# stock.net
KiCad netlist of a schematic drawn in EAGLE
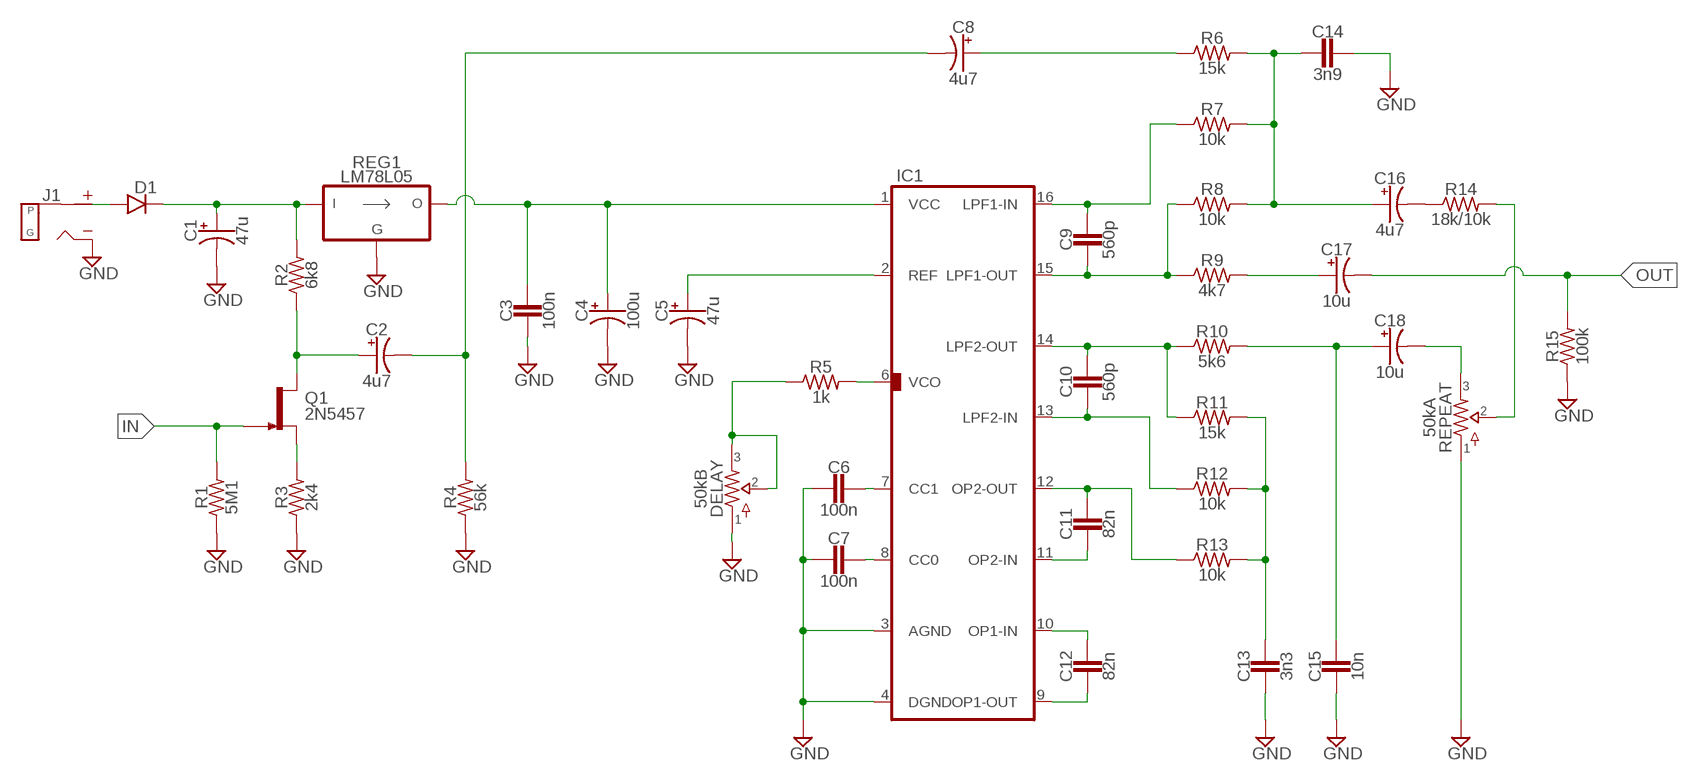
[diagram p0: schematic, sheet 1]

(export (version "E")
  (design (tool "Eeschema 10.0.6"))
  (components
    (comp (ref "C1")
      (value "47u")
      (footprint "eagle-import:050_020_1")
      (libsource (lib "eagle-import") (part "0501"))
    )
    (comp (ref "C2")
      (value "4u7")
      (footprint "eagle-import:050_020_1")
      (libsource (lib "eagle-import") (part "0501"))
    )
    (comp (ref "C3")
      (value "100n")
      (footprint "eagle-import:050X030_025_2")
      (libsource (lib "eagle-import") (part "CER/FILM2"))
    )
    (comp (ref "C4")
      (value "100u")
      (footprint "eagle-import:050_020_1")
      (libsource (lib "eagle-import") (part "0501"))
    )
    (comp (ref "C5")
      (value "47u")
      (footprint "eagle-import:050_020_1")
      (libsource (lib "eagle-import") (part "0501"))
    )
    (comp (ref "C6")
      (value "100n")
      (footprint "eagle-import:050X030_025_2")
      (libsource (lib "eagle-import") (part "CER/FILM2"))
    )
    (comp (ref "C7")
      (value "100n")
      (footprint "eagle-import:050X030_025_2")
      (libsource (lib "eagle-import") (part "CER/FILM2"))
    )
    (comp (ref "C8")
      (value "4u7")
      (footprint "eagle-import:050_020_1")
      (libsource (lib "eagle-import") (part "0501"))
    )
    (comp (ref "C9")
      (value "560p")
      (footprint "eagle-import:050X030_025_2")
      (libsource (lib "eagle-import") (part "CER/FILM2"))
    )
    (comp (ref "C10")
      (value "560p")
      (footprint "eagle-import:050X030_025_2")
      (libsource (lib "eagle-import") (part "CER/FILM2"))
    )
    (comp (ref "C11")
      (value "82n")
      (footprint "eagle-import:050X030_025_2")
      (libsource (lib "eagle-import") (part "CER/FILM2"))
    )
    (comp (ref "C12")
      (value "82n")
      (footprint "eagle-import:050X030_025_2")
      (libsource (lib "eagle-import") (part "CER/FILM2"))
    )
    (comp (ref "C13")
      (value "3n3")
      (footprint "eagle-import:050X030_025_2")
      (libsource (lib "eagle-import") (part "CER/FILM2"))
    )
    (comp (ref "C14")
      (value "3n9")
      (footprint "eagle-import:050X030_025_2")
      (libsource (lib "eagle-import") (part "CER/FILM2"))
    )
    (comp (ref "C15")
      (value "10n")
      (footprint "eagle-import:050X030_025_2")
      (libsource (lib "eagle-import") (part "CER/FILM2"))
    )
    (comp (ref "C16")
      (value "4u7")
      (footprint "eagle-import:050_020_1")
      (libsource (lib "eagle-import") (part "0501"))
    )
    (comp (ref "C17")
      (value "10u")
      (footprint "eagle-import:050_020_1")
      (libsource (lib "eagle-import") (part "0501"))
    )
    (comp (ref "C18")
      (value "10u")
      (footprint "eagle-import:050_020_1")
      (libsource (lib "eagle-import") (part "0501"))
    )
    (comp (ref "D1")
      (value "DO41.3")
      (footprint "eagle-import:DO41-3")
      (libsource (lib "eagle-import") (part "DO41.3"))
    )
    (comp (ref "DELAY")
      (value "50kB")
      (footprint "eagle-import:PADS_SMALL")
      (libsource (lib "eagle-import") (part "POTSSMALL_PADS"))
    )
    (comp (ref "IC1")
      (value "PT2399TH")
      (footprint "eagle-import:DIL16")
      (libsource (lib "eagle-import") (part "PT2399TH"))
    )
    (comp (ref "J1")
      (value "DC_MONO")
      (footprint "eagle-import:DC")
      (libsource (lib "eagle-import") (part "DC_MONO"))
    )
    (comp (ref "Q1")
      (value "2N5457")
      (footprint "eagle-import:TO92-")
      (libsource (lib "eagle-import") (part "2N5457"))
    )
    (comp (ref "R1")
      (value "5M1")
      (footprint "eagle-import:R0207_2V")
      (libsource (lib "eagle-import") (part "R_.2"))
    )
    (comp (ref "R2")
      (value "6k8")
      (footprint "eagle-import:R0207_2V")
      (libsource (lib "eagle-import") (part "R_.2"))
    )
    (comp (ref "R3")
      (value "2k4")
      (footprint "eagle-import:R0207_2V")
      (libsource (lib "eagle-import") (part "R_.2"))
    )
    (comp (ref "R4")
      (value "56k")
      (footprint "eagle-import:R0207_2V")
      (libsource (lib "eagle-import") (part "R_.2"))
    )
    (comp (ref "R5")
      (value "1k")
      (footprint "eagle-import:R0207_2V")
      (libsource (lib "eagle-import") (part "R_.2"))
    )
    (comp (ref "R6")
      (value "15k")
      (footprint "eagle-import:R0207_2V")
      (libsource (lib "eagle-import") (part "R_.2"))
    )
    (comp (ref "R7")
      (value "10k")
      (footprint "eagle-import:R0207_2V")
      (libsource (lib "eagle-import") (part "R_.2"))
    )
    (comp (ref "R8")
      (value "10k")
      (footprint "eagle-import:R0207_2V")
      (libsource (lib "eagle-import") (part "R_.2"))
    )
    (comp (ref "R9")
      (value "4k7")
      (footprint "eagle-import:R0207_2V")
      (libsource (lib "eagle-import") (part "R_.2"))
    )
    (comp (ref "R10")
      (value "5k6")
      (footprint "eagle-import:R0207_2V")
      (libsource (lib "eagle-import") (part "R_.2"))
    )
    (comp (ref "R11")
      (value "15k")
      (footprint "eagle-import:R0207_2V")
      (libsource (lib "eagle-import") (part "R_.2"))
    )
    (comp (ref "R12")
      (value "10k")
      (footprint "eagle-import:R0207_2V")
      (libsource (lib "eagle-import") (part "R_.2"))
    )
    (comp (ref "R13")
      (value "10k")
      (footprint "eagle-import:R0207_2V")
      (libsource (lib "eagle-import") (part "R_.2"))
    )
    (comp (ref "R14")
      (value "18k/10k")
      (footprint "eagle-import:R0207_2V")
      (libsource (lib "eagle-import") (part "R_.2"))
    )
    (comp (ref "R15")
      (value "100k")
      (footprint "eagle-import:R0207_2V")
      (libsource (lib "eagle-import") (part "R_.2"))
    )
    (comp (ref "REG1")
      (value "LM78L05")
      (footprint "eagle-import:TO92-")
      (libsource (lib "eagle-import") (part "LM78L05"))
    )
    (comp (ref "REPEAT")
      (value "50kA")
      (footprint "eagle-import:PADS_SMALL")
      (libsource (lib "eagle-import") (part "POTSSMALL_PADS"))
    )
  )
  (nets
    (net (code "1") (name "GND") (class "Default")
      (node (ref "C1") (pin "-") (pinfunction "-_-") (pintype "passive"))
      (node (ref "C13") (pin "2") (pinfunction "2_2") (pintype "passive"))
      (node (ref "C14") (pin "1") (pinfunction "1_1") (pintype "passive"))
      (node (ref "C15") (pin "2") (pinfunction "2_2") (pintype "passive"))
      (node (ref "C3") (pin "2") (pinfunction "2_2") (pintype "passive"))
      (node (ref "C4") (pin "-") (pinfunction "-_-") (pintype "passive"))
      (node (ref "C5") (pin "-") (pinfunction "-_-") (pintype "passive"))
      (node (ref "C6") (pin "2") (pinfunction "2_2") (pintype "passive"))
      (node (ref "C7") (pin "2") (pinfunction "2_2") (pintype "passive"))
      (node (ref "DELAY") (pin "1") (pinfunction "1_1") (pintype "passive"))
      (node (ref "IC1") (pin "3") (pinfunction "AGND_3") (pintype "power_in"))
      (node (ref "IC1") (pin "4") (pinfunction "DGND_4") (pintype "power_in"))
      (node (ref "J1") (pin "S") (pinfunction "SLEEVE_S") (pintype "passive"))
      (node (ref "R1") (pin "1") (pinfunction "1_1") (pintype "passive"))
      (node (ref "R15") (pin "1") (pinfunction "1_1") (pintype "passive"))
      (node (ref "R3") (pin "1") (pinfunction "1_1") (pintype "passive"))
      (node (ref "R4") (pin "1") (pinfunction "1_1") (pintype "passive"))
      (node (ref "REG1") (pin "2") (pinfunction "GND_2") (pintype "passive"))
      (node (ref "REPEAT") (pin "1") (pinfunction "1_1") (pintype "passive"))
    )
    (net (code "2") (name "IN") (class "Default")
      (node (ref "Q1") (pin "1") (pinfunction "G_1") (pintype "passive"))
      (node (ref "R1") (pin "2") (pinfunction "2_2") (pintype "passive"))
    )
    (net (code "3") (name "Net-(C2-Pad-)") (class "Default")
      (node (ref "C2") (pin "-") (pinfunction "-_-") (pintype "passive"))
      (node (ref "C8") (pin "-") (pinfunction "-_-") (pintype "passive"))
      (node (ref "R4") (pin "2") (pinfunction "2_2") (pintype "passive"))
    )
    (net (code "4") (name "Net-(C8-Pad+)") (class "Default")
      (node (ref "C8") (pin "+") (pinfunction "+_+") (pintype "passive"))
      (node (ref "R6") (pin "1") (pinfunction "1_1") (pintype "passive"))
    )
    (net (code "5") (name "Net-(C13-Pad1)") (class "Default")
      (node (ref "C13") (pin "1") (pinfunction "1_1") (pintype "passive"))
      (node (ref "R11") (pin "2") (pinfunction "2_2") (pintype "passive"))
      (node (ref "R12") (pin "2") (pinfunction "2_2") (pintype "passive"))
      (node (ref "R13") (pin "2") (pinfunction "2_2") (pintype "passive"))
    )
    (net (code "6") (name "Net-(C14-Pad2)") (class "Default")
      (node (ref "C14") (pin "2") (pinfunction "2_2") (pintype "passive"))
      (node (ref "C16") (pin "+") (pinfunction "+_+") (pintype "passive"))
      (node (ref "R6") (pin "2") (pinfunction "2_2") (pintype "passive"))
      (node (ref "R7") (pin "2") (pinfunction "2_2") (pintype "passive"))
      (node (ref "R8") (pin "2") (pinfunction "2_2") (pintype "passive"))
    )
    (net (code "7") (name "Net-(C15-Pad1)") (class "Default")
      (node (ref "C15") (pin "1") (pinfunction "1_1") (pintype "passive"))
      (node (ref "C18") (pin "+") (pinfunction "+_+") (pintype "passive"))
      (node (ref "R10") (pin "2") (pinfunction "2_2") (pintype "passive"))
    )
    (net (code "8") (name "Net-(C16-Pad-)") (class "Default")
      (node (ref "C16") (pin "-") (pinfunction "-_-") (pintype "passive"))
      (node (ref "R14") (pin "1") (pinfunction "1_1") (pintype "passive"))
    )
    (net (code "9") (name "Net-(C17-Pad+)") (class "Default")
      (node (ref "C17") (pin "+") (pinfunction "+_+") (pintype "passive"))
      (node (ref "R9") (pin "2") (pinfunction "2_2") (pintype "passive"))
    )
    (net (code "10") (name "Net-(C18-Pad-)") (class "Default")
      (node (ref "C18") (pin "-") (pinfunction "-_-") (pintype "passive"))
      (node (ref "REPEAT") (pin "3") (pinfunction "3_3") (pintype "passive"))
    )
    (net (code "11") (name "Net-(DELAY-Pad2)") (class "Default")
      (node (ref "DELAY") (pin "2") (pinfunction "2_2") (pintype "passive"))
      (node (ref "DELAY") (pin "3") (pinfunction "3_3") (pintype "passive"))
      (node (ref "R5") (pin "1") (pinfunction "1_1") (pintype "passive"))
    )
    (net (code "12") (name "Net-(IC1-CC0)") (class "Default")
      (node (ref "C7") (pin "1") (pinfunction "1_1") (pintype "passive"))
      (node (ref "IC1") (pin "8") (pinfunction "CC0_8") (pintype "input"))
    )
    (net (code "13") (name "Net-(IC1-CC1)") (class "Default")
      (node (ref "C6") (pin "1") (pinfunction "1_1") (pintype "passive"))
      (node (ref "IC1") (pin "7") (pinfunction "CC1_7") (pintype "input"))
    )
    (net (code "14") (name "Net-(IC1-LPF1-IN)") (class "Default")
      (node (ref "C9") (pin "1") (pinfunction "1_1") (pintype "passive"))
      (node (ref "IC1") (pin "16") (pinfunction "LPF1-IN_16") (pintype "input"))
      (node (ref "R7") (pin "1") (pinfunction "1_1") (pintype "passive"))
    )
    (net (code "15") (name "Net-(IC1-LPF1-OUT)") (class "Default")
      (node (ref "C9") (pin "2") (pinfunction "2_2") (pintype "passive"))
      (node (ref "IC1") (pin "15") (pinfunction "LPF1-OUT_15") (pintype "output"))
      (node (ref "R8") (pin "1") (pinfunction "1_1") (pintype "passive"))
      (node (ref "R9") (pin "1") (pinfunction "1_1") (pintype "passive"))
    )
    (net (code "16") (name "Net-(IC1-LPF2-IN)") (class "Default")
      (node (ref "C10") (pin "2") (pinfunction "2_2") (pintype "passive"))
      (node (ref "IC1") (pin "13") (pinfunction "LPF2-IN_13") (pintype "input"))
      (node (ref "R12") (pin "1") (pinfunction "1_1") (pintype "passive"))
    )
    (net (code "17") (name "Net-(IC1-LPF2-OUT)") (class "Default")
      (node (ref "C10") (pin "1") (pinfunction "1_1") (pintype "passive"))
      (node (ref "IC1") (pin "14") (pinfunction "LPF2-OUT_14") (pintype "output"))
      (node (ref "R10") (pin "1") (pinfunction "1_1") (pintype "passive"))
      (node (ref "R11") (pin "1") (pinfunction "1_1") (pintype "passive"))
    )
    (net (code "18") (name "Net-(IC1-OP1-IN)") (class "Default")
      (node (ref "C12") (pin "1") (pinfunction "1_1") (pintype "passive"))
      (node (ref "IC1") (pin "10") (pinfunction "OP1-IN_10") (pintype "input"))
    )
    (net (code "19") (name "Net-(IC1-OP1-OUT)") (class "Default")
      (node (ref "C12") (pin "2") (pinfunction "2_2") (pintype "passive"))
      (node (ref "IC1") (pin "9") (pinfunction "OP1-OUT_9") (pintype "output"))
    )
    (net (code "20") (name "Net-(IC1-OP2-IN)") (class "Default")
      (node (ref "C11") (pin "2") (pinfunction "2_2") (pintype "passive"))
      (node (ref "IC1") (pin "11") (pinfunction "OP2-IN_11") (pintype "input"))
    )
    (net (code "21") (name "Net-(IC1-OP2-OUT)") (class "Default")
      (node (ref "C11") (pin "1") (pinfunction "1_1") (pintype "passive"))
      (node (ref "IC1") (pin "12") (pinfunction "OP2-OUT_12") (pintype "output"))
      (node (ref "R13") (pin "1") (pinfunction "1_1") (pintype "passive"))
    )
    (net (code "22") (name "Net-(IC1-REF)") (class "Default")
      (node (ref "C5") (pin "+") (pinfunction "+_+") (pintype "passive"))
      (node (ref "IC1") (pin "2") (pinfunction "REF_2") (pintype "input"))
    )
    (net (code "23") (name "Net-(IC1-VCC)") (class "Default")
      (node (ref "C3") (pin "1") (pinfunction "1_1") (pintype "passive"))
      (node (ref "C4") (pin "+") (pinfunction "+_+") (pintype "passive"))
      (node (ref "IC1") (pin "1") (pinfunction "VCC_1") (pintype "power_in"))
      (node (ref "REG1") (pin "3") (pinfunction "VO_3") (pintype "passive"))
    )
    (net (code "24") (name "Net-(IC1-VCO)") (class "Default")
      (node (ref "IC1") (pin "6") (pinfunction "VCO_6") (pintype "input"))
      (node (ref "R5") (pin "2") (pinfunction "2_2") (pintype "passive"))
    )
    (net (code "25") (name "Net-(J1-TIP)") (class "Default")
      (node (ref "D1") (pin "A") (pinfunction "A_A") (pintype "passive"))
      (node (ref "J1") (pin "T") (pinfunction "TIP_T") (pintype "passive"))
    )
    (net (code "26") (name "Net-(Q1-D)") (class "Default")
      (node (ref "C2") (pin "+") (pinfunction "+_+") (pintype "passive"))
      (node (ref "Q1") (pin "3") (pinfunction "D_3") (pintype "passive"))
      (node (ref "R2") (pin "1") (pinfunction "1_1") (pintype "passive"))
    )
    (net (code "27") (name "Net-(Q1-S)") (class "Default")
      (node (ref "Q1") (pin "2") (pinfunction "S_2") (pintype "passive"))
      (node (ref "R3") (pin "2") (pinfunction "2_2") (pintype "passive"))
    )
    (net (code "28") (name "Net-(R14-Pad2)") (class "Default")
      (node (ref "R14") (pin "2") (pinfunction "2_2") (pintype "passive"))
      (node (ref "REPEAT") (pin "2") (pinfunction "2_2") (pintype "passive"))
    )
    (net (code "29") (name "Net-(REG1-VI)") (class "Default")
      (node (ref "C1") (pin "+") (pinfunction "+_+") (pintype "passive"))
      (node (ref "D1") (pin "C") (pinfunction "C_C") (pintype "passive"))
      (node (ref "R2") (pin "2") (pinfunction "2_2") (pintype "passive"))
      (node (ref "REG1") (pin "1") (pinfunction "VI_1") (pintype "input"))
    )
    (net (code "30") (name "OUT") (class "Default")
      (node (ref "C17") (pin "-") (pinfunction "-_-") (pintype "passive"))
      (node (ref "R15") (pin "2") (pinfunction "2_2") (pintype "passive"))
    )
  )
)
